# Sheet1.net
KiCad netlist of a schematic drawn in Altium Designer
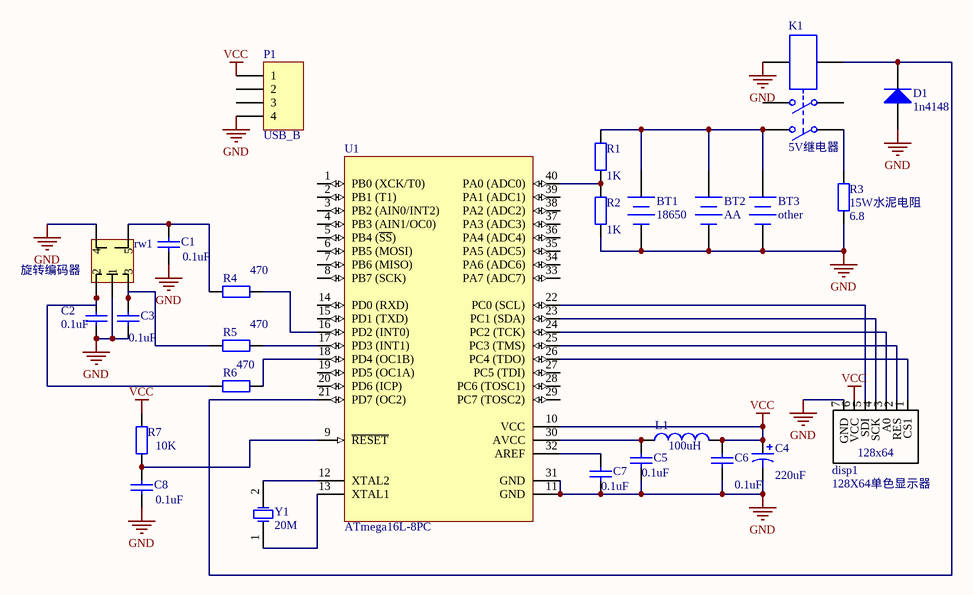
[diagram p0: Sheet1.SchDoc]

(export (version "E")
  (design (tool "Eeschema 10.0.6"))
  (components
    (comp (ref "BT1")
      (value "18650")
      (footprint "shsPcbLib:18650battery")
      (description "Multicell Battery")
      (fields (field (name "PUBLISHER") "Altium Limited"))
      (libsource (lib "Miscellaneous Devices") (part "Battery"))
    )
    (comp (ref "BT2")
      (value "AA")
      (footprint "shsPcbLib:aabattery")
      (description "Multicell Battery")
      (fields (field (name "PUBLISHER") "Altium Limited"))
      (libsource (lib "Miscellaneous Devices") (part "Battery"))
    )
    (comp (ref "BT3")
      (value "other")
      (footprint "shsPcbLib:Header2_3.96")
      (description "Multicell Battery")
      (fields (field (name "PUBLISHER") "Altium Limited"))
      (libsource (lib "Miscellaneous Devices") (part "Battery"))
    )
    (comp (ref "C1")
      (value "0.1uF")
      (footprint "RAD-0.2")
      (description "Capacitor")
      (fields (field (name "Comment") "Cap") (field (name "PUBLISHER") "Altium Limited"))
      (libsource (lib "Miscellaneous Devices") (part "Cap"))
    )
    (comp (ref "C2")
      (value "0.1uF")
      (footprint "RAD-0.2")
      (description "Capacitor")
      (fields (field (name "Comment") "Cap") (field (name "PUBLISHER") "Altium Limited"))
      (libsource (lib "Miscellaneous Devices") (part "Cap"))
    )
    (comp (ref "C3")
      (value "0.1uF")
      (footprint "RAD-0.2")
      (description "Capacitor")
      (fields (field (name "Comment") "Cap") (field (name "PUBLISHER") "Altium Limited"))
      (libsource (lib "Miscellaneous Devices") (part "Cap"))
    )
    (comp (ref "C4")
      (value "220uF")
      (footprint "RB5-10.5")
      (description "Polarized Capacitor (Radial)")
      (fields (field (name "Comment") "Cap Pol1") (field (name "PUBLISHER") "Altium Limited"))
      (libsource (lib "Miscellaneous Devices") (part "Cap Pol1"))
    )
    (comp (ref "C5")
      (value "0.1uF")
      (footprint "RAD-0.2")
      (description "Capacitor")
      (fields (field (name "Comment") "Cap") (field (name "PUBLISHER") "Altium Limited"))
      (libsource (lib "Miscellaneous Devices") (part "Cap"))
    )
    (comp (ref "C6")
      (value "0.1uF")
      (footprint "RAD-0.2")
      (description "Capacitor")
      (fields (field (name "Comment") "Cap") (field (name "PUBLISHER") "Altium Limited"))
      (libsource (lib "Miscellaneous Devices") (part "Cap"))
    )
    (comp (ref "C7")
      (value "0.1uF")
      (footprint "RAD-0.2")
      (description "Capacitor")
      (fields (field (name "Comment") "Cap") (field (name "PUBLISHER") "Altium Limited"))
      (libsource (lib "Miscellaneous Devices") (part "Cap"))
    )
    (comp (ref "C8")
      (value "0.1uF")
      (footprint "RAD-0.2")
      (description "Capacitor")
      (fields (field (name "Comment") "Cap") (field (name "PUBLISHER") "Altium Limited"))
      (libsource (lib "Miscellaneous Devices") (part "Cap"))
    )
    (comp (ref "D1")
      (value "1n4148")
      (footprint "DIO10.46-5.3x2.8")
      (description "1 Amp General Purpose Rectifier")
      (fields (field (name "PUBLISHER") "Altium Limited"))
      (libsource (lib "Miscellaneous Devices") (part "Diode 1N4001"))
    )
    (comp (ref "disp1")
      (value "128X64单色显示器")
      (footprint "mzl05_12864")
      (libsource (lib "Integrated_Library1") (part "mzl05_12864"))
    )
    (comp (ref "K1")
      (value "5V继电器")
      (footprint "shsPcbLib:5vrelay")
      (description "Dual-Pole Single-Throw Relay")
      (fields (field (name "PUBLISHER") "Altium Limited"))
      (libsource (lib "Miscellaneous Devices") (part "Relay-DPST"))
    )
    (comp (ref "L1")
      (value "100uH")
      (footprint "AXIAL-0.5")
      (description "Inductor")
      (fields (field (name "PUBLISHER") "Altium Limited"))
      (libsource (lib "Miscellaneous Devices") (part "Inductor"))
    )
    (comp (ref "P1")
      (value "USB_B")
      (footprint "shsPcbLib:USB_B")
      (description "Header, 4-Pin")
      (fields (field (name "PUBLISHER") "Altium Limited"))
      (libsource (lib "Miscellaneous Connectors") (part "Header 4"))
    )
    (comp (ref "R1")
      (value "1K")
      (footprint "AXIAL-0.4")
      (description "Resistor")
      (fields (field (name "Comment") "Res2") (field (name "PUBLISHER") "Altium Limited"))
      (libsource (lib "Miscellaneous Devices") (part "Res2"))
    )
    (comp (ref "R2")
      (value "1K")
      (footprint "AXIAL-0.4")
      (description "Resistor")
      (fields (field (name "Comment") "Res2") (field (name "PUBLISHER") "Altium Limited"))
      (libsource (lib "Miscellaneous Devices") (part "Res2"))
    )
    (comp (ref "R3")
      (value "15W水泥电阻")
      (footprint "shsPcbLib:R_15W")
      (description "Resistor")
      (fields (field (name "ALTIUM_VALUE") "6.8") (field (name "PUBLISHER") "Altium Limited"))
      (libsource (lib "Miscellaneous Devices") (part "Res2"))
    )
    (comp (ref "R4")
      (value "470")
      (footprint "AXIAL-0.4")
      (description "Resistor")
      (fields (field (name "Comment") "Res2") (field (name "PUBLISHER") "Altium Limited"))
      (libsource (lib "") (part "Res2_1"))
    )
    (comp (ref "R5")
      (value "470")
      (footprint "AXIAL-0.4")
      (description "Resistor")
      (fields (field (name "Comment") "Res2") (field (name "PUBLISHER") "Altium Limited"))
      (libsource (lib "") (part "Res2_1"))
    )
    (comp (ref "R6")
      (value "470")
      (footprint "AXIAL-0.4")
      (description "Resistor")
      (fields (field (name "Comment") "Res2") (field (name "PUBLISHER") "Altium Limited"))
      (libsource (lib "") (part "Res2_1"))
    )
    (comp (ref "R7")
      (value "10K")
      (footprint "AXIAL-0.4")
      (description "Resistor")
      (fields (field (name "Comment") "Res2") (field (name "PUBLISHER") "Altium Limited"))
      (libsource (lib "Miscellaneous Devices") (part "Res2"))
    )
    (comp (ref "rw1")
      (value "旋转编码器")
      (footprint "shsPcbLib:rotate_switch")
      (libsource (lib "Integrated_Library1") (part "rotate_switch"))
    )
    (comp (ref "U1")
      (value "ATmega16L-8PC")
      (footprint "40P6")
      (description "8-Bit AVR Microcontroller with 16K Bytes of In-System Programmable Flash Memory")
      (fields (field (name "PUBLISHER") "Altium Limited"))
      (libsource (lib "Atmel Microcontroller 8-Bit AVR") (part "ATmega16L-8PC"))
    )
    (comp (ref "Y1")
      (value "20M")
      (footprint "shsPcbLib:XTAL")
      (description "Crystal Oscillator")
      (fields (field (name "PUBLISHER") "Altium Limited"))
      (libsource (lib "Miscellaneous Devices") (part "XTAL"))
    )
  )
  (nets
    (net (code "1") (name "GND") (class "Default")
      (node (ref "BT1") (pin "2") (pinfunction "-_2") (pintype "passive"))
      (node (ref "BT2") (pin "2") (pinfunction "-_2") (pintype "passive"))
      (node (ref "BT3") (pin "2") (pinfunction "-_2") (pintype "passive"))
      (node (ref "C1") (pin "2") (pinfunction "2_2") (pintype "passive"))
      (node (ref "C2") (pin "2") (pinfunction "2_2") (pintype "passive"))
      (node (ref "C3") (pin "2") (pinfunction "2_2") (pintype "passive"))
      (node (ref "C4") (pin "2") (pinfunction "2_2") (pintype "passive"))
      (node (ref "C5") (pin "1") (pinfunction "1_1") (pintype "passive"))
      (node (ref "C6") (pin "2") (pinfunction "2_2") (pintype "passive"))
      (node (ref "C7") (pin "1") (pinfunction "1_1") (pintype "passive"))
      (node (ref "C8") (pin "1") (pinfunction "1_1") (pintype "passive"))
      (node (ref "D1") (pin "1") (pinfunction "A_1") (pintype "passive"))
      (node (ref "K1") (pin "6") (pinfunction "6_6") (pintype "passive"))
      (node (ref "P1") (pin "4") (pinfunction "4_4") (pintype "passive"))
      (node (ref "R2") (pin "1") (pinfunction "1_1") (pintype "passive"))
      (node (ref "R3") (pin "1") (pinfunction "1_1") (pintype "passive"))
      (node (ref "U1") (pin "11") (pinfunction "GND_11") (pintype "power_in"))
      (node (ref "U1") (pin "31") (pinfunction "GND_31") (pintype "power_in"))
      (node (ref "disp1") (pin "7") (pinfunction "GND_7") (pintype "passive"))
      (node (ref "rw1") (pin "1") (pinfunction "1_1") (pintype "passive"))
      (node (ref "rw1") (pin "4") (pinfunction "4_4") (pintype "passive"))
    )
    (net (code "2") (name "Net-(BT1-+)") (class "Default")
      (node (ref "BT1") (pin "1") (pinfunction "+_1") (pintype "passive"))
      (node (ref "BT2") (pin "1") (pinfunction "+_1") (pintype "passive"))
      (node (ref "BT3") (pin "1") (pinfunction "+_1") (pintype "passive"))
      (node (ref "K1") (pin "2") (pinfunction "2_2") (pintype "passive"))
      (node (ref "R1") (pin "2") (pinfunction "2_2") (pintype "passive"))
    )
    (net (code "3") (name "Net-(C1-Pad1)") (class "Default")
      (node (ref "C1") (pin "1") (pinfunction "1_1") (pintype "passive"))
      (node (ref "R4") (pin "1") (pinfunction "1_1") (pintype "passive"))
      (node (ref "rw1") (pin "5") (pinfunction "5_5") (pintype "passive"))
    )
    (net (code "4") (name "Net-(C2-Pad1)") (class "Default")
      (node (ref "C2") (pin "1") (pinfunction "1_1") (pintype "passive"))
      (node (ref "R6") (pin "1") (pinfunction "1_1") (pintype "passive"))
      (node (ref "rw1") (pin "2") (pinfunction "2_2") (pintype "passive"))
    )
    (net (code "5") (name "Net-(C3-Pad1)") (class "Default")
      (node (ref "C3") (pin "1") (pinfunction "1_1") (pintype "passive"))
      (node (ref "R5") (pin "1") (pinfunction "1_1") (pintype "passive"))
      (node (ref "rw1") (pin "3") (pinfunction "3_3") (pintype "passive"))
    )
    (net (code "6") (name "Net-(D1-K)") (class "Default")
      (node (ref "D1") (pin "2") (pinfunction "K_2") (pintype "passive"))
      (node (ref "K1") (pin "5") (pinfunction "5_5") (pintype "passive"))
      (node (ref "U1") (pin "21") (pinfunction "PD7_(OC2)_21") (pintype "bidirectional"))
    )
    (net (code "7") (name "Net-(K1-Pad1)") (class "Default")
      (node (ref "K1") (pin "1") (pinfunction "1_1") (pintype "passive"))
      (node (ref "R3") (pin "2") (pinfunction "2_2") (pintype "passive"))
    )
    (net (code "8") (name "Net-(U1-AREF)") (class "Default")
      (node (ref "C7") (pin "2") (pinfunction "2_2") (pintype "passive"))
      (node (ref "U1") (pin "32") (pinfunction "AREF_32") (pintype "passive"))
    )
    (net (code "9") (name "Net-(U1-AVCC)") (class "Default")
      (node (ref "C5") (pin "2") (pinfunction "2_2") (pintype "passive"))
      (node (ref "L1") (pin "1") (pinfunction "1_1") (pintype "passive"))
      (node (ref "U1") (pin "30") (pinfunction "AVCC_30") (pintype "power_in"))
    )
    (net (code "10") (name "Net-(U1-PA0_(ADC0))") (class "Default")
      (node (ref "R1") (pin "1") (pinfunction "1_1") (pintype "passive"))
      (node (ref "R2") (pin "2") (pinfunction "2_2") (pintype "passive"))
      (node (ref "U1") (pin "40") (pinfunction "PA0_(ADC0)_40") (pintype "bidirectional"))
    )
    (net (code "11") (name "Net-(U1-PC0_(SCL))") (class "Default")
      (node (ref "U1") (pin "22") (pinfunction "PC0_(SCL)_22") (pintype "bidirectional"))
      (node (ref "disp1") (pin "5") (pinfunction "SDI_5") (pintype "passive"))
    )
    (net (code "12") (name "Net-(U1-PC1_(SDA))") (class "Default")
      (node (ref "U1") (pin "23") (pinfunction "PC1_(SDA)_23") (pintype "bidirectional"))
      (node (ref "disp1") (pin "4") (pinfunction "SCK_4") (pintype "passive"))
    )
    (net (code "13") (name "Net-(U1-PC2_(TCK))") (class "Default")
      (node (ref "U1") (pin "24") (pinfunction "PC2_(TCK)_24") (pintype "bidirectional"))
      (node (ref "disp1") (pin "3") (pinfunction "A0_3") (pintype "passive"))
    )
    (net (code "14") (name "Net-(U1-PC3_(TMS))") (class "Default")
      (node (ref "U1") (pin "25") (pinfunction "PC3_(TMS)_25") (pintype "bidirectional"))
      (node (ref "disp1") (pin "2") (pinfunction "RES_2") (pintype "passive"))
    )
    (net (code "15") (name "Net-(U1-PC4_(TDO))") (class "Default")
      (node (ref "U1") (pin "26") (pinfunction "PC4_(TDO)_26") (pintype "bidirectional"))
      (node (ref "disp1") (pin "1") (pinfunction "CS1_1") (pintype "passive"))
    )
    (net (code "16") (name "Net-(U1-PD2_(INT0))") (class "Default")
      (node (ref "R4") (pin "2") (pinfunction "2_2") (pintype "passive"))
      (node (ref "U1") (pin "16") (pinfunction "PD2_(INT0)_16") (pintype "bidirectional"))
    )
    (net (code "17") (name "Net-(U1-PD3_(INT1))") (class "Default")
      (node (ref "R5") (pin "2") (pinfunction "2_2") (pintype "passive"))
      (node (ref "U1") (pin "17") (pinfunction "PD3_(INT1)_17") (pintype "bidirectional"))
    )
    (net (code "18") (name "Net-(U1-PD4_(OC1B))") (class "Default")
      (node (ref "R6") (pin "2") (pinfunction "2_2") (pintype "passive"))
      (node (ref "U1") (pin "18") (pinfunction "PD4_(OC1B)_18") (pintype "bidirectional"))
    )
    (net (code "19") (name "Net-(U1-XTAL1)") (class "Default")
      (node (ref "U1") (pin "13") (pinfunction "XTAL1_13") (pintype "passive"))
      (node (ref "Y1") (pin "1") (pinfunction "OSC1_1") (pintype "passive"))
    )
    (net (code "20") (name "Net-(U1-XTAL2)") (class "Default")
      (node (ref "U1") (pin "12") (pinfunction "XTAL2_12") (pintype "passive"))
      (node (ref "Y1") (pin "2") (pinfunction "OSC2_2") (pintype "passive"))
    )
    (net (code "21") (name "Net-(U1-~{RESET})") (class "Default")
      (node (ref "C8") (pin "2") (pinfunction "2_2") (pintype "passive"))
      (node (ref "R7") (pin "1") (pinfunction "1_1") (pintype "passive"))
      (node (ref "U1") (pin "9") (pinfunction "~{RESET}_9") (pintype "input"))
    )
    (net (code "22") (name "VCC") (class "Default")
      (node (ref "C4") (pin "1") (pinfunction "1_1") (pintype "passive"))
      (node (ref "C6") (pin "1") (pinfunction "1_1") (pintype "passive"))
      (node (ref "L1") (pin "2") (pinfunction "2_2") (pintype "passive"))
      (node (ref "P1") (pin "1") (pinfunction "1_1") (pintype "passive"))
      (node (ref "R7") (pin "2") (pinfunction "2_2") (pintype "passive"))
      (node (ref "U1") (pin "10") (pinfunction "VCC_10") (pintype "power_in"))
      (node (ref "disp1") (pin "6") (pinfunction "VCC_6") (pintype "passive"))
    )
    (net (code "23") (name "unconnected-(K1-Pad3)") (class "Default")
      (node (ref "K1") (pin "3") (pinfunction "3_3") (pintype "passive"))
    )
    (net (code "24") (name "unconnected-(K1-Pad4)") (class "Default")
      (node (ref "K1") (pin "4") (pinfunction "4_4") (pintype "passive"))
    )
    (net (code "25") (name "unconnected-(P1-Pad2)") (class "Default")
      (node (ref "P1") (pin "2") (pinfunction "2_2") (pintype "passive"))
    )
    (net (code "26") (name "unconnected-(P1-Pad3)") (class "Default")
      (node (ref "P1") (pin "3") (pinfunction "3_3") (pintype "passive"))
    )
    (net (code "27") (name "unconnected-(U1-PA1_(ADC1)-Pad39)") (class "Default")
      (node (ref "U1") (pin "39") (pinfunction "PA1_(ADC1)_39") (pintype "bidirectional"))
    )
    (net (code "28") (name "unconnected-(U1-PA2_(ADC2)-Pad38)") (class "Default")
      (node (ref "U1") (pin "38") (pinfunction "PA2_(ADC2)_38") (pintype "bidirectional"))
    )
    (net (code "29") (name "unconnected-(U1-PA3_(ADC3)-Pad37)") (class "Default")
      (node (ref "U1") (pin "37") (pinfunction "PA3_(ADC3)_37") (pintype "bidirectional"))
    )
    (net (code "30") (name "unconnected-(U1-PA4_(ADC4)-Pad36)") (class "Default")
      (node (ref "U1") (pin "36") (pinfunction "PA4_(ADC4)_36") (pintype "bidirectional"))
    )
    (net (code "31") (name "unconnected-(U1-PA5_(ADC5)-Pad35)") (class "Default")
      (node (ref "U1") (pin "35") (pinfunction "PA5_(ADC5)_35") (pintype "bidirectional"))
    )
    (net (code "32") (name "unconnected-(U1-PA6_(ADC6)-Pad34)") (class "Default")
      (node (ref "U1") (pin "34") (pinfunction "PA6_(ADC6)_34") (pintype "bidirectional"))
    )
    (net (code "33") (name "unconnected-(U1-PA7_(ADC7)-Pad33)") (class "Default")
      (node (ref "U1") (pin "33") (pinfunction "PA7_(ADC7)_33") (pintype "bidirectional"))
    )
    (net (code "34") (name "unconnected-(U1-PB0_(XCK{slash}T0)-Pad1)") (class "Default")
      (node (ref "U1") (pin "1") (pinfunction "PB0_(XCK/T0)_1") (pintype "bidirectional"))
    )
    (net (code "35") (name "unconnected-(U1-PB1_(T1)-Pad2)") (class "Default")
      (node (ref "U1") (pin "2") (pinfunction "PB1_(T1)_2") (pintype "bidirectional"))
    )
    (net (code "36") (name "unconnected-(U1-PB2_(AIN0{slash}INT2)-Pad3)") (class "Default")
      (node (ref "U1") (pin "3") (pinfunction "PB2_(AIN0/INT2)_3") (pintype "bidirectional"))
    )
    (net (code "37") (name "unconnected-(U1-PB3_(AIN1{slash}OC0)-Pad4)") (class "Default")
      (node (ref "U1") (pin "4") (pinfunction "PB3_(AIN1/OC0)_4") (pintype "bidirectional"))
    )
    (net (code "38") (name "unconnected-(U1-PB4_(~{SS})-Pad5)") (class "Default")
      (node (ref "U1") (pin "5") (pinfunction "PB4_(~{SS})_5") (pintype "bidirectional"))
    )
    (net (code "39") (name "unconnected-(U1-PB5_(MOSI)-Pad6)") (class "Default")
      (node (ref "U1") (pin "6") (pinfunction "PB5_(MOSI)_6") (pintype "bidirectional"))
    )
    (net (code "40") (name "unconnected-(U1-PB6_(MISO)-Pad7)") (class "Default")
      (node (ref "U1") (pin "7") (pinfunction "PB6_(MISO)_7") (pintype "bidirectional"))
    )
    (net (code "41") (name "unconnected-(U1-PB7_(SCK)-Pad8)") (class "Default")
      (node (ref "U1") (pin "8") (pinfunction "PB7_(SCK)_8") (pintype "bidirectional"))
    )
    (net (code "42") (name "unconnected-(U1-PC5_(TDI)-Pad27)") (class "Default")
      (node (ref "U1") (pin "27") (pinfunction "PC5_(TDI)_27") (pintype "bidirectional"))
    )
    (net (code "43") (name "unconnected-(U1-PC6_(TOSC1)-Pad28)") (class "Default")
      (node (ref "U1") (pin "28") (pinfunction "PC6_(TOSC1)_28") (pintype "bidirectional"))
    )
    (net (code "44") (name "unconnected-(U1-PC7_(TOSC2)-Pad29)") (class "Default")
      (node (ref "U1") (pin "29") (pinfunction "PC7_(TOSC2)_29") (pintype "bidirectional"))
    )
    (net (code "45") (name "unconnected-(U1-PD0_(RXD)-Pad14)") (class "Default")
      (node (ref "U1") (pin "14") (pinfunction "PD0_(RXD)_14") (pintype "bidirectional"))
    )
    (net (code "46") (name "unconnected-(U1-PD1_(TXD)-Pad15)") (class "Default")
      (node (ref "U1") (pin "15") (pinfunction "PD1_(TXD)_15") (pintype "bidirectional"))
    )
    (net (code "47") (name "unconnected-(U1-PD5_(OC1A)-Pad19)") (class "Default")
      (node (ref "U1") (pin "19") (pinfunction "PD5_(OC1A)_19") (pintype "bidirectional"))
    )
    (net (code "48") (name "unconnected-(U1-PD6_(ICP)-Pad20)") (class "Default")
      (node (ref "U1") (pin "20") (pinfunction "PD6_(ICP)_20") (pintype "bidirectional"))
    )
  )
)
